# ADS7924.net
KiCad netlist of a schematic drawn in Altium Designer
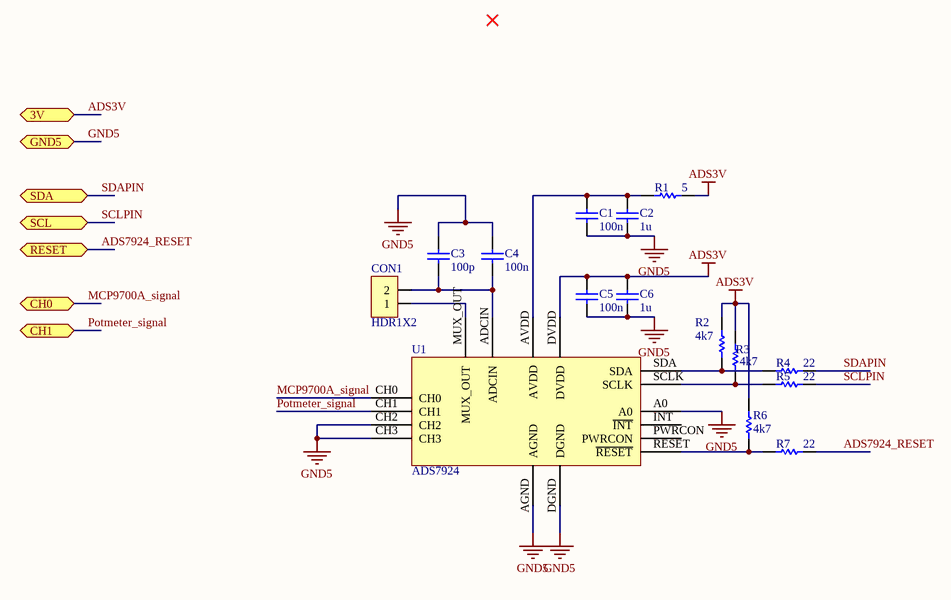
[diagram p0: ADS7924.SchDoc]

(export (version "E")
  (design (tool "Eeschema 10.0.6"))
  (components
    (comp (ref "C1")
      (value "100n")
      (footprint "dimploma:0805C")
      (libsource (lib "diploma") (part "CAPACITOR"))
    )
    (comp (ref "C2") (value "1u") (footprint "dimploma:0805C") (libsource (lib "diploma") (part "CAPACITOR")))
    (comp (ref "C3")
      (value "100p")
      (footprint "dimploma:0805C")
      (libsource (lib "diploma") (part "CAPACITOR"))
    )
    (comp (ref "C4")
      (value "100n")
      (footprint "dimploma:0805C")
      (libsource (lib "diploma") (part "CAPACITOR"))
    )
    (comp (ref "C5")
      (value "100n")
      (footprint "dimploma:0805C")
      (libsource (lib "diploma") (part "CAPACITOR"))
    )
    (comp (ref "C6") (value "1u") (footprint "dimploma:0805C") (libsource (lib "diploma") (part "CAPACITOR")))
    (comp (ref "CON1")
      (value "HDR1X2")
      (footprint "dimploma:HDR1X2RAST")
      (libsource (lib "diploma") (part "HDR1X2"))
    )
    (comp (ref "R1") (value "5") (footprint "dimploma:0805R") (libsource (lib "diploma") (part "RESISTOR")))
    (comp (ref "R2") (value "4k7") (footprint "dimploma:0805R") (libsource (lib "diploma") (part "RESISTOR")))
    (comp (ref "R3") (value "4k7") (footprint "dimploma:0805R") (libsource (lib "diploma") (part "RESISTOR")))
    (comp (ref "R4") (value "22") (footprint "dimploma:0805R") (libsource (lib "diploma") (part "RESISTOR")))
    (comp (ref "R5") (value "22") (footprint "dimploma:0805R") (libsource (lib "diploma") (part "RESISTOR")))
    (comp (ref "R6") (value "4k7") (footprint "dimploma:0805R") (libsource (lib "diploma") (part "RESISTOR")))
    (comp (ref "R7") (value "22") (footprint "dimploma:0805R") (libsource (lib "diploma") (part "RESISTOR")))
    (comp (ref "U1")
      (value "ADS7924")
      (footprint "dimploma:QFN16 - HAND")
      (libsource (lib "diploma") (part "ADS7924"))
    )
  )
  (nets
    (net (code "1") (name "/ADS7924_RESET") (class "Default")
      (node (ref "R7") (pin "1") (pinfunction "1_1") (pintype "passive"))
    )
    (net (code "2") (name "/MCP9700A_signal") (class "Default")
      (node (ref "U1") (pin "CH0") (pinfunction "CH0_CH0") (pintype "passive"))
    )
    (net (code "3") (name "/Potmeter_signal") (class "Default")
      (node (ref "U1") (pin "CH1") (pinfunction "CH1_CH1") (pintype "passive"))
    )
    (net (code "4") (name "/SCLPIN") (class "Default")
      (node (ref "R5") (pin "1") (pinfunction "1_1") (pintype "passive"))
    )
    (net (code "5") (name "/SDAPIN") (class "Default")
      (node (ref "R4") (pin "1") (pinfunction "1_1") (pintype "passive"))
    )
    (net (code "6") (name "ADS3V") (class "Default")
      (node (ref "C5") (pin "2") (pinfunction "2_2") (pintype "passive"))
      (node (ref "C6") (pin "2") (pinfunction "2_2") (pintype "passive"))
      (node (ref "R1") (pin "2") (pinfunction "2_2") (pintype "passive"))
      (node (ref "R2") (pin "2") (pinfunction "2_2") (pintype "passive"))
      (node (ref "R3") (pin "2") (pinfunction "2_2") (pintype "passive"))
      (node (ref "R6") (pin "2") (pinfunction "2_2") (pintype "passive"))
      (node (ref "U1") (pin "DVDD") (pinfunction "DVDD_DVDD") (pintype "passive"))
    )
    (net (code "7") (name "GND5") (class "Default")
      (node (ref "C1") (pin "1") (pinfunction "1_1") (pintype "passive"))
      (node (ref "C2") (pin "1") (pinfunction "1_1") (pintype "passive"))
      (node (ref "C3") (pin "2") (pinfunction "2_2") (pintype "passive"))
      (node (ref "C4") (pin "2") (pinfunction "2_2") (pintype "passive"))
      (node (ref "C5") (pin "1") (pinfunction "1_1") (pintype "passive"))
      (node (ref "C6") (pin "1") (pinfunction "1_1") (pintype "passive"))
      (node (ref "U1") (pin "A0") (pinfunction "A0_A0") (pintype "passive"))
      (node (ref "U1") (pin "AGND") (pinfunction "AGND_AGND") (pintype "passive"))
      (node (ref "U1") (pin "CH2") (pinfunction "CH2_CH2") (pintype "passive"))
      (node (ref "U1") (pin "CH3") (pinfunction "CH3_CH3") (pintype "passive"))
      (node (ref "U1") (pin "DGND") (pinfunction "DGND_DGND") (pintype "passive"))
    )
    (net (code "8") (name "Net-(C1-Pad2)") (class "Default")
      (node (ref "C1") (pin "2") (pinfunction "2_2") (pintype "passive"))
      (node (ref "C2") (pin "2") (pinfunction "2_2") (pintype "passive"))
      (node (ref "R1") (pin "1") (pinfunction "1_1") (pintype "passive"))
      (node (ref "U1") (pin "AVDD") (pinfunction "AVDD_AVDD") (pintype "passive"))
    )
    (net (code "9") (name "Net-(C3-Pad1)") (class "Default")
      (node (ref "C3") (pin "1") (pinfunction "1_1") (pintype "passive"))
      (node (ref "C4") (pin "1") (pinfunction "1_1") (pintype "passive"))
      (node (ref "CON1") (pin "2") (pinfunction "2_2") (pintype "passive"))
      (node (ref "U1") (pin "ADCIN") (pinfunction "ADCIN_ADCIN") (pintype "passive"))
    )
    (net (code "10") (name "Net-(CON1-Pad1)") (class "Default")
      (node (ref "CON1") (pin "1") (pinfunction "1_1") (pintype "passive"))
      (node (ref "U1") (pin "MUX_OUT") (pinfunction "MUX_OUT_MUX_OUT") (pintype "passive"))
    )
    (net (code "11") (name "Net-(R2-Pad1)") (class "Default")
      (node (ref "R2") (pin "1") (pinfunction "1_1") (pintype "passive"))
      (node (ref "R4") (pin "2") (pinfunction "2_2") (pintype "passive"))
      (node (ref "U1") (pin "SDA") (pinfunction "SDA_SDA") (pintype "passive"))
    )
    (net (code "12") (name "Net-(R3-Pad1)") (class "Default")
      (node (ref "R3") (pin "1") (pinfunction "1_1") (pintype "passive"))
      (node (ref "R5") (pin "2") (pinfunction "2_2") (pintype "passive"))
      (node (ref "U1") (pin "SCLK") (pinfunction "SCLK_SCLK") (pintype "passive"))
    )
    (net (code "13") (name "Net-(U1-~{RESET})") (class "Default")
      (node (ref "R6") (pin "1") (pinfunction "1_1") (pintype "passive"))
      (node (ref "R7") (pin "2") (pinfunction "2_2") (pintype "passive"))
      (node (ref "U1") (pin "RESET") (pinfunction "~{RESET}_RESET") (pintype "passive"))
    )
    (net (code "14") (name "unconnected-(U1-PadPWRCON)") (class "Default")
      (node (ref "U1") (pin "PWRCON") (pinfunction "PWRCON_PWRCON") (pintype "passive"))
    )
    (net (code "15") (name "unconnected-(U1-~{INT}-PadINT)") (class "Default")
      (node (ref "U1") (pin "INT") (pinfunction "~{INT}_INT") (pintype "passive"))
    )
  )
)
